# Sheet2.net
KiCad netlist of a schematic drawn in Altium Designer
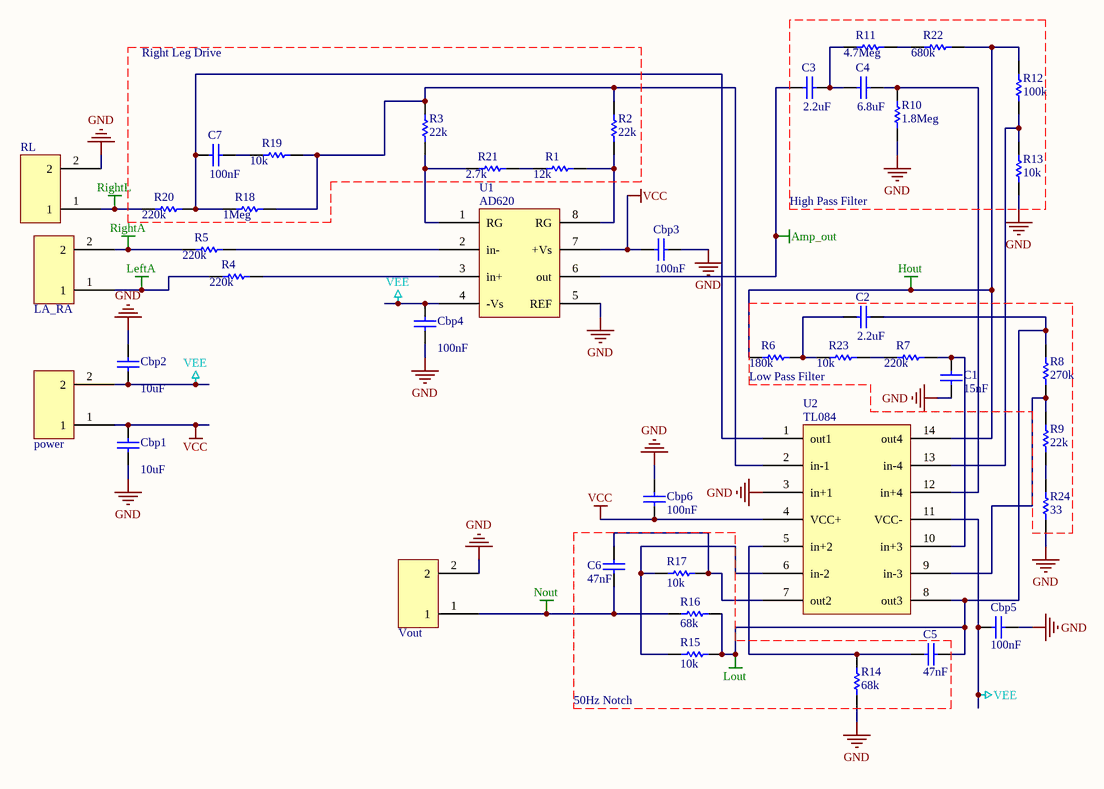
[diagram p0: Sheet2.SchDoc]

(export (version "E")
  (design (tool "Eeschema 10.0.6"))
  (components
    (comp (ref "C1")
      (value "15nF")
      (footprint "cap")
      (description "Capacitor")
      (fields (field (name "Comment") "Cap") (field (name "PUBLISHER") "Altium Limited"))
      (libsource (lib "Miscellaneous Devices") (part "Cap"))
    )
    (comp (ref "C2")
      (value "2.2uF")
      (footprint "cap")
      (description "Capacitor")
      (fields (field (name "Comment") "Cap") (field (name "PUBLISHER") "Altium Limited"))
      (libsource (lib "Miscellaneous Devices") (part "Cap"))
    )
    (comp (ref "C3")
      (value "2.2uF")
      (footprint "cap")
      (description "Capacitor")
      (fields (field (name "Comment") "Cap") (field (name "PUBLISHER") "Altium Limited"))
      (libsource (lib "Miscellaneous Devices") (part "Cap"))
    )
    (comp (ref "C4")
      (value "6.8uF")
      (footprint "cap")
      (description "Capacitor")
      (fields (field (name "Comment") "Cap") (field (name "PUBLISHER") "Altium Limited"))
      (libsource (lib "Miscellaneous Devices") (part "Cap"))
    )
    (comp (ref "C5")
      (value "47nF")
      (footprint "cap")
      (description "Capacitor")
      (fields (field (name "Comment") "Cap") (field (name "PUBLISHER") "Altium Limited"))
      (libsource (lib "Miscellaneous Devices") (part "Cap"))
    )
    (comp (ref "C6")
      (value "47nF")
      (footprint "cap")
      (description "Capacitor")
      (fields (field (name "Comment") "Cap") (field (name "PUBLISHER") "Altium Limited"))
      (libsource (lib "Miscellaneous Devices") (part "Cap"))
    )
    (comp (ref "C7")
      (value "100nF")
      (footprint "cap")
      (description "Capacitor")
      (fields (field (name "Comment") "Cap") (field (name "PUBLISHER") "Altium Limited"))
      (libsource (lib "Miscellaneous Devices") (part "Cap"))
    )
    (comp (ref "Cbp1")
      (value "10uF")
      (footprint "cap")
      (description "Capacitor")
      (fields (field (name "Comment") "Cap") (field (name "PUBLISHER") "Altium Limited"))
      (libsource (lib "Miscellaneous Devices") (part "Cap"))
    )
    (comp (ref "Cbp2")
      (value "10uF")
      (footprint "cap")
      (description "Capacitor")
      (fields (field (name "Comment") "Cap") (field (name "PUBLISHER") "Altium Limited"))
      (libsource (lib "Miscellaneous Devices") (part "Cap"))
    )
    (comp (ref "Cbp3")
      (value "100nF")
      (footprint "cap")
      (description "Capacitor")
      (fields (field (name "Comment") "Cap") (field (name "PUBLISHER") "Altium Limited"))
      (libsource (lib "Miscellaneous Devices") (part "Cap"))
    )
    (comp (ref "Cbp4")
      (value "100nF")
      (footprint "cap")
      (description "Capacitor")
      (fields (field (name "Comment") "Cap") (field (name "PUBLISHER") "Altium Limited"))
      (libsource (lib "Miscellaneous Devices") (part "Cap"))
    )
    (comp (ref "Cbp5")
      (value "100nF")
      (footprint "cap")
      (description "Capacitor")
      (fields (field (name "Comment") "Cap") (field (name "PUBLISHER") "Altium Limited"))
      (libsource (lib "Miscellaneous Devices") (part "Cap"))
    )
    (comp (ref "Cbp6")
      (value "100nF")
      (footprint "cap")
      (description "Capacitor")
      (fields (field (name "Comment") "Cap") (field (name "PUBLISHER") "Altium Limited"))
      (libsource (lib "Miscellaneous Devices") (part "Cap"))
    )
    (comp (ref "LA_RA") (value "port") (footprint "pinheader") (libsource (lib "Schlib1") (part "port")))
    (comp (ref "power") (value "port") (footprint "pinheader") (libsource (lib "Schlib1") (part "port")))
    (comp (ref "R1")
      (value "12k")
      (footprint "res")
      (description "Semiconductor Resistor")
      (fields (field (name "Comment") "Res Semi") (field (name "PUBLISHER") "Altium Limited"))
      (libsource (lib "Miscellaneous Devices") (part "Res Semi"))
    )
    (comp (ref "R2")
      (value "22k")
      (footprint "res")
      (description "Semiconductor Resistor")
      (fields (field (name "Comment") "Res Semi") (field (name "PUBLISHER") "Altium Limited"))
      (libsource (lib "Miscellaneous Devices") (part "Res Semi"))
    )
    (comp (ref "R3")
      (value "22k")
      (footprint "res")
      (description "Semiconductor Resistor")
      (fields (field (name "Comment") "Res Semi") (field (name "PUBLISHER") "Altium Limited"))
      (libsource (lib "Miscellaneous Devices") (part "Res Semi"))
    )
    (comp (ref "R4")
      (value "220k")
      (footprint "res")
      (description "Semiconductor Resistor")
      (fields (field (name "Comment") "Res Semi") (field (name "PUBLISHER") "Altium Limited"))
      (libsource (lib "Miscellaneous Devices") (part "Res Semi"))
    )
    (comp (ref "R5")
      (value "220k")
      (footprint "res")
      (description "Semiconductor Resistor")
      (fields (field (name "Comment") "Res Semi") (field (name "PUBLISHER") "Altium Limited"))
      (libsource (lib "Miscellaneous Devices") (part "Res Semi"))
    )
    (comp (ref "R6")
      (value "180k")
      (footprint "res")
      (description "Semiconductor Resistor")
      (fields (field (name "Comment") "Res Semi") (field (name "PUBLISHER") "Altium Limited"))
      (libsource (lib "Miscellaneous Devices") (part "Res Semi"))
    )
    (comp (ref "R7")
      (value "220k")
      (footprint "res")
      (description "Semiconductor Resistor")
      (fields (field (name "Comment") "Res Semi") (field (name "PUBLISHER") "Altium Limited"))
      (libsource (lib "Miscellaneous Devices") (part "Res Semi"))
    )
    (comp (ref "R8")
      (value "270k")
      (footprint "res")
      (description "Semiconductor Resistor")
      (fields (field (name "Comment") "Res Semi") (field (name "PUBLISHER") "Altium Limited"))
      (libsource (lib "Miscellaneous Devices") (part "Res Semi"))
    )
    (comp (ref "R9")
      (value "22k")
      (footprint "res")
      (description "Semiconductor Resistor")
      (fields (field (name "Comment") "Res Semi") (field (name "PUBLISHER") "Altium Limited"))
      (libsource (lib "Miscellaneous Devices") (part "Res Semi"))
    )
    (comp (ref "R10")
      (value "1.8Meg")
      (footprint "res")
      (description "Semiconductor Resistor")
      (fields (field (name "Comment") "Res Semi") (field (name "PUBLISHER") "Altium Limited"))
      (libsource (lib "Miscellaneous Devices") (part "Res Semi"))
    )
    (comp (ref "R11")
      (value "4.7Meg")
      (footprint "res")
      (description "Semiconductor Resistor")
      (fields (field (name "Comment") "Res Semi") (field (name "PUBLISHER") "Altium Limited"))
      (libsource (lib "Miscellaneous Devices") (part "Res Semi"))
    )
    (comp (ref "R12")
      (value "100k")
      (footprint "res")
      (description "Semiconductor Resistor")
      (fields (field (name "Comment") "Res Semi") (field (name "PUBLISHER") "Altium Limited"))
      (libsource (lib "Miscellaneous Devices") (part "Res Semi"))
    )
    (comp (ref "R13")
      (value "10k")
      (footprint "res")
      (description "Semiconductor Resistor")
      (fields (field (name "Comment") "Res Semi") (field (name "PUBLISHER") "Altium Limited"))
      (libsource (lib "Miscellaneous Devices") (part "Res Semi"))
    )
    (comp (ref "R14")
      (value "68k")
      (footprint "res")
      (description "Semiconductor Resistor")
      (fields (field (name "Comment") "Res Semi") (field (name "PUBLISHER") "Altium Limited"))
      (libsource (lib "Miscellaneous Devices") (part "Res Semi"))
    )
    (comp (ref "R15")
      (value "10k")
      (footprint "res")
      (description "Semiconductor Resistor")
      (fields (field (name "Comment") "Res Semi") (field (name "PUBLISHER") "Altium Limited"))
      (libsource (lib "Miscellaneous Devices") (part "Res Semi"))
    )
    (comp (ref "R16")
      (value "68k")
      (footprint "res")
      (description "Semiconductor Resistor")
      (fields (field (name "Comment") "Res Semi") (field (name "PUBLISHER") "Altium Limited"))
      (libsource (lib "Miscellaneous Devices") (part "Res Semi"))
    )
    (comp (ref "R17")
      (value "10k")
      (footprint "res")
      (description "Semiconductor Resistor")
      (fields (field (name "Comment") "Res Semi") (field (name "PUBLISHER") "Altium Limited"))
      (libsource (lib "Miscellaneous Devices") (part "Res Semi"))
    )
    (comp (ref "R18")
      (value "1Meg")
      (footprint "res")
      (description "Semiconductor Resistor")
      (fields (field (name "Comment") "Res Semi") (field (name "PUBLISHER") "Altium Limited"))
      (libsource (lib "Miscellaneous Devices") (part "Res Semi"))
    )
    (comp (ref "R19")
      (value "10k")
      (footprint "res")
      (description "Semiconductor Resistor")
      (fields (field (name "Comment") "Res Semi") (field (name "PUBLISHER") "Altium Limited"))
      (libsource (lib "Miscellaneous Devices") (part "Res Semi"))
    )
    (comp (ref "R20")
      (value "220k")
      (footprint "res")
      (description "Semiconductor Resistor")
      (fields (field (name "Comment") "Res Semi") (field (name "PUBLISHER") "Altium Limited"))
      (libsource (lib "Miscellaneous Devices") (part "Res Semi"))
    )
    (comp (ref "R21")
      (value "2.7k")
      (footprint "res")
      (description "Semiconductor Resistor")
      (fields (field (name "Comment") "Res Semi") (field (name "PUBLISHER") "Altium Limited"))
      (libsource (lib "Miscellaneous Devices") (part "Res Semi"))
    )
    (comp (ref "R22")
      (value "680k")
      (footprint "res")
      (description "Semiconductor Resistor")
      (fields (field (name "Comment") "Res Semi") (field (name "PUBLISHER") "Altium Limited"))
      (libsource (lib "Miscellaneous Devices") (part "Res Semi"))
    )
    (comp (ref "R23")
      (value "10k")
      (footprint "res")
      (description "Semiconductor Resistor")
      (fields (field (name "Comment") "Res Semi") (field (name "PUBLISHER") "Altium Limited"))
      (libsource (lib "Miscellaneous Devices") (part "Res Semi"))
    )
    (comp (ref "R24")
      (value "33")
      (footprint "res")
      (description "Semiconductor Resistor")
      (fields (field (name "Comment") "Res Semi") (field (name "PUBLISHER") "Altium Limited"))
      (libsource (lib "Miscellaneous Devices") (part "Res Semi"))
    )
    (comp (ref "RL") (value "port") (footprint "pinheader") (libsource (lib "Schlib1") (part "port")))
    (comp (ref "U1") (value "AD620") (footprint "AD620") (libsource (lib "Schlib1") (part "AD620")))
    (comp (ref "U2") (value "TL084") (footprint "TL084") (libsource (lib "Schlib1") (part "TL084")))
    (comp (ref "Vout") (value "port") (footprint "pinheader") (libsource (lib "Schlib1") (part "port")))
  )
  (nets
    (net (code "1") (name "Amp_out") (class "Default")
      (node (ref "C3") (pin "1") (pinfunction "1_1") (pintype "passive"))
      (node (ref "U1") (pin "6") (pinfunction "out_6") (pintype "passive"))
    )
    (net (code "2") (name "GND") (class "Default")
      (node (ref "C1") (pin "1") (pinfunction "1_1") (pintype "passive"))
      (node (ref "Cbp1") (pin "1") (pinfunction "1_1") (pintype "passive"))
      (node (ref "Cbp2") (pin "2") (pinfunction "2_2") (pintype "passive"))
      (node (ref "Cbp3") (pin "2") (pinfunction "2_2") (pintype "passive"))
      (node (ref "Cbp4") (pin "1") (pinfunction "1_1") (pintype "passive"))
      (node (ref "Cbp5") (pin "1") (pinfunction "1_1") (pintype "passive"))
      (node (ref "Cbp6") (pin "1") (pinfunction "1_1") (pintype "passive"))
      (node (ref "R10") (pin "1") (pinfunction "1_1") (pintype "passive"))
      (node (ref "R13") (pin "1") (pinfunction "1_1") (pintype "passive"))
      (node (ref "R14") (pin "1") (pinfunction "1_1") (pintype "passive"))
      (node (ref "R24") (pin "1") (pinfunction "1_1") (pintype "passive"))
      (node (ref "RL") (pin "2") (pinfunction "2_2") (pintype "passive"))
      (node (ref "U1") (pin "5") (pinfunction "REF_5") (pintype "passive"))
      (node (ref "U2") (pin "3") (pinfunction "in+1_3") (pintype "passive"))
      (node (ref "Vout") (pin "2") (pinfunction "2_2") (pintype "passive"))
    )
    (net (code "3") (name "Hout") (class "Default")
      (node (ref "R12") (pin "2") (pinfunction "2_2") (pintype "passive"))
      (node (ref "R22") (pin "2") (pinfunction "2_2") (pintype "passive"))
      (node (ref "R6") (pin "1") (pinfunction "1_1") (pintype "passive"))
      (node (ref "U2") (pin "14") (pinfunction "out4_14") (pintype "passive"))
    )
    (net (code "4") (name "LeftA") (class "Default")
      (node (ref "LA_RA") (pin "1") (pinfunction "1_1") (pintype "passive"))
      (node (ref "R4") (pin "1") (pinfunction "1_1") (pintype "passive"))
    )
    (net (code "5") (name "Lout") (class "Default")
      (node (ref "C2") (pin "2") (pinfunction "2_2") (pintype "passive"))
      (node (ref "C5") (pin "1") (pinfunction "1_1") (pintype "passive"))
      (node (ref "R15") (pin "2") (pinfunction "2_2") (pintype "passive"))
      (node (ref "R16") (pin "2") (pinfunction "2_2") (pintype "passive"))
      (node (ref "R8") (pin "2") (pinfunction "2_2") (pintype "passive"))
      (node (ref "U2") (pin "8") (pinfunction "out3_8") (pintype "passive"))
    )
    (net (code "6") (name "Net-(C2-Pad1)") (class "Default")
      (node (ref "C2") (pin "1") (pinfunction "1_1") (pintype "passive"))
      (node (ref "R23") (pin "1") (pinfunction "1_1") (pintype "passive"))
      (node (ref "R6") (pin "2") (pinfunction "2_2") (pintype "passive"))
    )
    (net (code "7") (name "Net-(C3-Pad2)") (class "Default")
      (node (ref "C3") (pin "2") (pinfunction "2_2") (pintype "passive"))
      (node (ref "C4") (pin "1") (pinfunction "1_1") (pintype "passive"))
      (node (ref "R11") (pin "1") (pinfunction "1_1") (pintype "passive"))
    )
    (net (code "8") (name "Net-(C7-Pad2)") (class "Default")
      (node (ref "C7") (pin "2") (pinfunction "2_2") (pintype "passive"))
      (node (ref "R19") (pin "1") (pinfunction "1_1") (pintype "passive"))
    )
    (net (code "9") (name "Net-(R1-Pad1)") (class "Default")
      (node (ref "R1") (pin "1") (pinfunction "1_1") (pintype "passive"))
      (node (ref "R21") (pin "2") (pinfunction "2_2") (pintype "passive"))
    )
    (net (code "10") (name "Net-(R1-Pad2)") (class "Default")
      (node (ref "R1") (pin "2") (pinfunction "2_2") (pintype "passive"))
      (node (ref "R2") (pin "1") (pinfunction "1_1") (pintype "passive"))
      (node (ref "U1") (pin "8") (pinfunction "RG_8") (pintype "passive"))
    )
    (net (code "11") (name "Net-(R11-Pad2)") (class "Default")
      (node (ref "R11") (pin "2") (pinfunction "2_2") (pintype "passive"))
      (node (ref "R22") (pin "1") (pinfunction "1_1") (pintype "passive"))
    )
    (net (code "12") (name "Net-(R21-Pad1)") (class "Default")
      (node (ref "R21") (pin "1") (pinfunction "1_1") (pintype "passive"))
      (node (ref "R3") (pin "2") (pinfunction "2_2") (pintype "passive"))
      (node (ref "U1") (pin "1") (pinfunction "RG_1") (pintype "passive"))
    )
    (net (code "13") (name "Net-(R23-Pad2)") (class "Default")
      (node (ref "R23") (pin "2") (pinfunction "2_2") (pintype "passive"))
      (node (ref "R7") (pin "1") (pinfunction "1_1") (pintype "passive"))
    )
    (net (code "14") (name "Net-(R24-Pad2)") (class "Default")
      (node (ref "R24") (pin "2") (pinfunction "2_2") (pintype "passive"))
      (node (ref "R9") (pin "1") (pinfunction "1_1") (pintype "passive"))
    )
    (net (code "15") (name "Net-(U1-in+)") (class "Default")
      (node (ref "R4") (pin "2") (pinfunction "2_2") (pintype "passive"))
      (node (ref "U1") (pin "3") (pinfunction "in+_3") (pintype "passive"))
    )
    (net (code "16") (name "Net-(U1-in-)") (class "Default")
      (node (ref "R5") (pin "2") (pinfunction "2_2") (pintype "passive"))
      (node (ref "U1") (pin "2") (pinfunction "in-_2") (pintype "passive"))
    )
    (net (code "17") (name "Net-(U2-in+2)") (class "Default")
      (node (ref "C5") (pin "2") (pinfunction "2_2") (pintype "passive"))
      (node (ref "R14") (pin "2") (pinfunction "2_2") (pintype "passive"))
      (node (ref "U2") (pin "5") (pinfunction "in+2_5") (pintype "passive"))
    )
    (net (code "18") (name "Net-(U2-in+3)") (class "Default")
      (node (ref "C1") (pin "2") (pinfunction "2_2") (pintype "passive"))
      (node (ref "R7") (pin "2") (pinfunction "2_2") (pintype "passive"))
      (node (ref "U2") (pin "10") (pinfunction "in+3_10") (pintype "passive"))
    )
    (net (code "19") (name "Net-(U2-in+4)") (class "Default")
      (node (ref "C4") (pin "2") (pinfunction "2_2") (pintype "passive"))
      (node (ref "R10") (pin "2") (pinfunction "2_2") (pintype "passive"))
      (node (ref "U2") (pin "12") (pinfunction "in+4_12") (pintype "passive"))
    )
    (net (code "20") (name "Net-(U2-in-1)") (class "Default")
      (node (ref "R18") (pin "2") (pinfunction "2_2") (pintype "passive"))
      (node (ref "R19") (pin "2") (pinfunction "2_2") (pintype "passive"))
      (node (ref "R2") (pin "2") (pinfunction "2_2") (pintype "passive"))
      (node (ref "R3") (pin "1") (pinfunction "1_1") (pintype "passive"))
      (node (ref "U2") (pin "2") (pinfunction "in-1_2") (pintype "passive"))
    )
    (net (code "21") (name "Net-(U2-in-2)") (class "Default")
      (node (ref "R15") (pin "1") (pinfunction "1_1") (pintype "passive"))
      (node (ref "R17") (pin "1") (pinfunction "1_1") (pintype "passive"))
      (node (ref "U2") (pin "6") (pinfunction "in-2_6") (pintype "passive"))
    )
    (net (code "22") (name "Net-(U2-in-3)") (class "Default")
      (node (ref "R8") (pin "1") (pinfunction "1_1") (pintype "passive"))
      (node (ref "R9") (pin "2") (pinfunction "2_2") (pintype "passive"))
      (node (ref "U2") (pin "9") (pinfunction "in-3_9") (pintype "passive"))
    )
    (net (code "23") (name "Net-(U2-in-4)") (class "Default")
      (node (ref "R12") (pin "1") (pinfunction "1_1") (pintype "passive"))
      (node (ref "R13") (pin "2") (pinfunction "2_2") (pintype "passive"))
      (node (ref "U2") (pin "13") (pinfunction "in-4_13") (pintype "passive"))
    )
    (net (code "24") (name "Net-(U2-out1)") (class "Default")
      (node (ref "C7") (pin "1") (pinfunction "1_1") (pintype "passive"))
      (node (ref "R18") (pin "1") (pinfunction "1_1") (pintype "passive"))
      (node (ref "R20") (pin "2") (pinfunction "2_2") (pintype "passive"))
      (node (ref "U2") (pin "1") (pinfunction "out1_1") (pintype "passive"))
    )
    (net (code "25") (name "Net-(U2-out2)") (class "Default")
      (node (ref "C6") (pin "2") (pinfunction "2_2") (pintype "passive"))
      (node (ref "R17") (pin "2") (pinfunction "2_2") (pintype "passive"))
      (node (ref "U2") (pin "7") (pinfunction "out2_7") (pintype "passive"))
    )
    (net (code "26") (name "Nout") (class "Default")
      (node (ref "C6") (pin "1") (pinfunction "1_1") (pintype "passive"))
      (node (ref "R16") (pin "1") (pinfunction "1_1") (pintype "passive"))
      (node (ref "Vout") (pin "1") (pinfunction "1_1") (pintype "passive"))
    )
    (net (code "27") (name "RightA") (class "Default")
      (node (ref "LA_RA") (pin "2") (pinfunction "2_2") (pintype "passive"))
      (node (ref "R5") (pin "1") (pinfunction "1_1") (pintype "passive"))
    )
    (net (code "28") (name "RightL") (class "Default")
      (node (ref "R20") (pin "1") (pinfunction "1_1") (pintype "passive"))
      (node (ref "RL") (pin "1") (pinfunction "1_1") (pintype "passive"))
    )
    (net (code "29") (name "VCC") (class "Default")
      (node (ref "Cbp1") (pin "2") (pinfunction "2_2") (pintype "passive"))
      (node (ref "Cbp3") (pin "1") (pinfunction "1_1") (pintype "passive"))
      (node (ref "Cbp6") (pin "2") (pinfunction "2_2") (pintype "passive"))
      (node (ref "U1") (pin "7") (pinfunction "+Vs_7") (pintype "passive"))
      (node (ref "U2") (pin "4") (pinfunction "VCC+_4") (pintype "passive"))
      (node (ref "power") (pin "1") (pinfunction "1_1") (pintype "passive"))
    )
    (net (code "30") (name "VEE") (class "Default")
      (node (ref "Cbp2") (pin "1") (pinfunction "1_1") (pintype "passive"))
      (node (ref "Cbp4") (pin "2") (pinfunction "2_2") (pintype "passive"))
      (node (ref "Cbp5") (pin "2") (pinfunction "2_2") (pintype "passive"))
      (node (ref "U1") (pin "4") (pinfunction "-Vs_4") (pintype "passive"))
      (node (ref "U2") (pin "11") (pinfunction "VCC-_11") (pintype "passive"))
      (node (ref "power") (pin "2") (pinfunction "2_2") (pintype "passive"))
    )
  )
)
